# Kivipallur_joonis1.net
KiCad netlist of a schematic drawn in Altium Designer
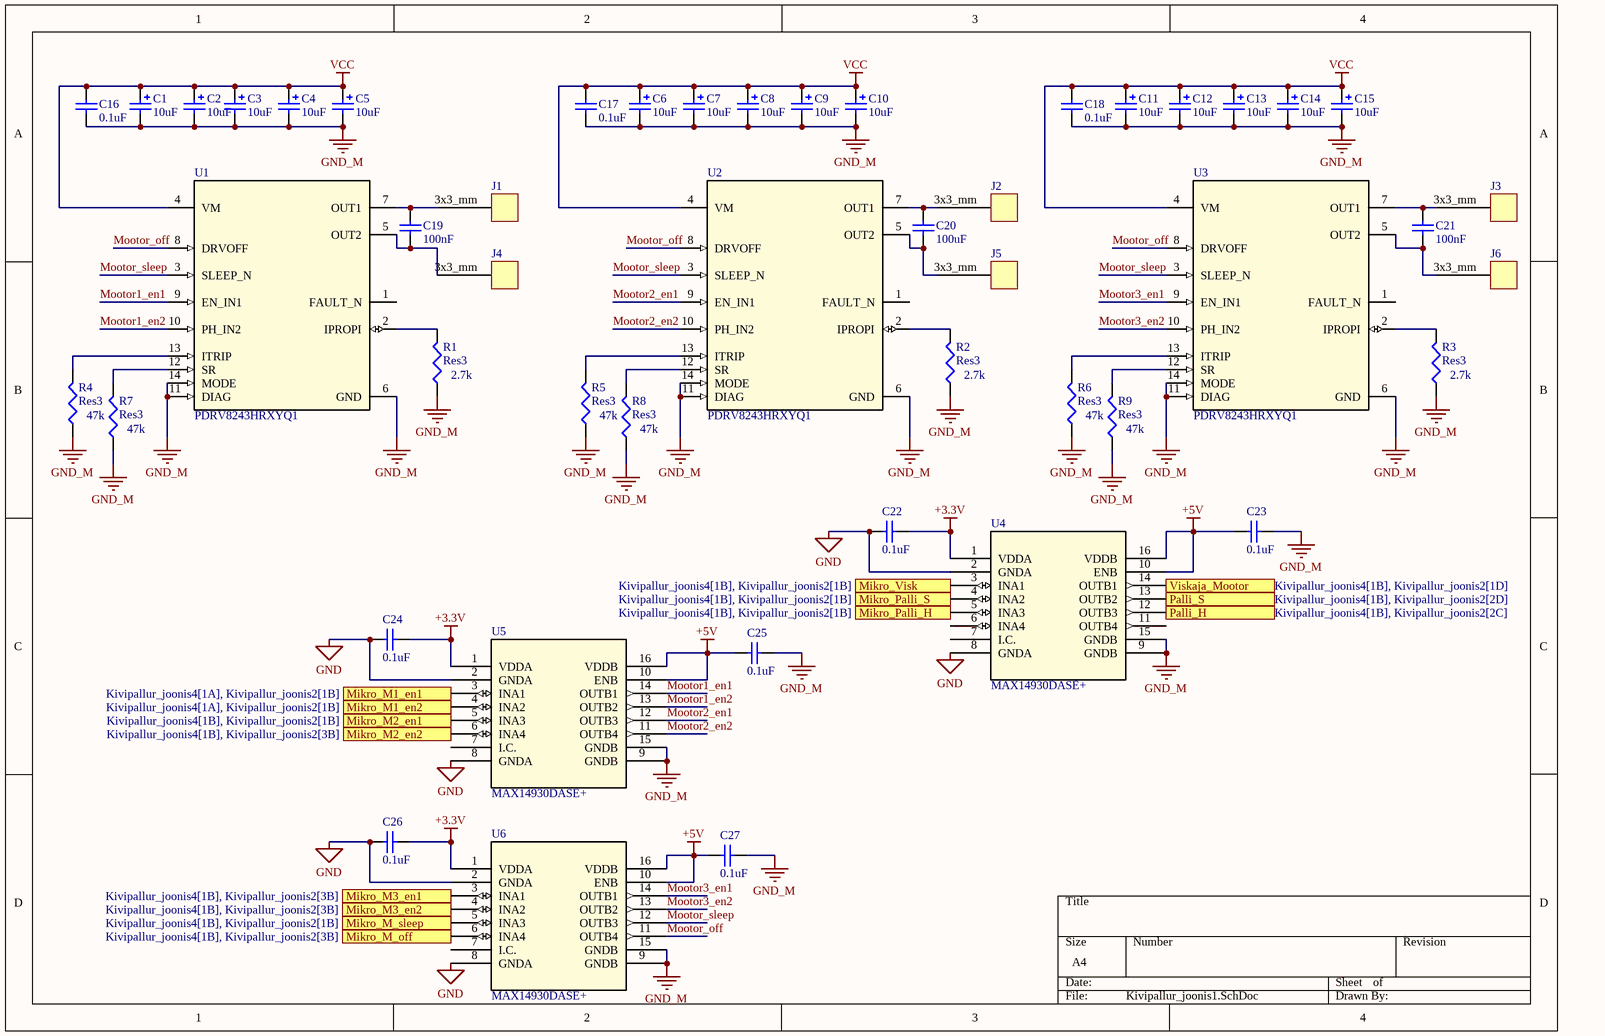
[diagram p0: Kivipallur_joonis1.SchDoc]

(export (version "E")
  (design (tool "Eeschema 10.0.6"))
  (components
    (comp (ref "C1")
      (value "10uF")
      (footprint "C0805")
      (description "Polarized Capacitor (Surface Mount)")
      (fields (field (name "Comment") "Cap Pol3") (field (name "PUBLISHER") "Altium Limited"))
      (libsource (lib "Miscellaneous Devices") (part "Cap Pol3"))
    )
    (comp (ref "C2")
      (value "10uF")
      (footprint "C0805")
      (description "Polarized Capacitor (Surface Mount)")
      (fields (field (name "Comment") "Cap Pol3") (field (name "PUBLISHER") "Altium Limited"))
      (libsource (lib "Miscellaneous Devices") (part "Cap Pol3"))
    )
    (comp (ref "C3")
      (value "10uF")
      (footprint "C0805")
      (description "Polarized Capacitor (Surface Mount)")
      (fields (field (name "Comment") "Cap Pol3") (field (name "PUBLISHER") "Altium Limited"))
      (libsource (lib "Miscellaneous Devices") (part "Cap Pol3"))
    )
    (comp (ref "C4")
      (value "10uF")
      (footprint "C0805")
      (description "Polarized Capacitor (Surface Mount)")
      (fields (field (name "Comment") "Cap Pol3") (field (name "PUBLISHER") "Altium Limited"))
      (libsource (lib "Miscellaneous Devices") (part "Cap Pol3"))
    )
    (comp (ref "C5")
      (value "10uF")
      (footprint "C0805")
      (description "Polarized Capacitor (Surface Mount)")
      (fields (field (name "Comment") "Cap Pol3") (field (name "PUBLISHER") "Altium Limited"))
      (libsource (lib "Miscellaneous Devices") (part "Cap Pol3"))
    )
    (comp (ref "C6")
      (value "10uF")
      (footprint "C0805")
      (description "Polarized Capacitor (Surface Mount)")
      (fields (field (name "Comment") "Cap Pol3") (field (name "PUBLISHER") "Altium Limited"))
      (libsource (lib "Miscellaneous Devices") (part "Cap Pol3"))
    )
    (comp (ref "C7")
      (value "10uF")
      (footprint "C0805")
      (description "Polarized Capacitor (Surface Mount)")
      (fields (field (name "Comment") "Cap Pol3") (field (name "PUBLISHER") "Altium Limited"))
      (libsource (lib "Miscellaneous Devices") (part "Cap Pol3"))
    )
    (comp (ref "C8")
      (value "10uF")
      (footprint "C0805")
      (description "Polarized Capacitor (Surface Mount)")
      (fields (field (name "Comment") "Cap Pol3") (field (name "PUBLISHER") "Altium Limited"))
      (libsource (lib "Miscellaneous Devices") (part "Cap Pol3"))
    )
    (comp (ref "C9")
      (value "10uF")
      (footprint "C0805")
      (description "Polarized Capacitor (Surface Mount)")
      (fields (field (name "Comment") "Cap Pol3") (field (name "PUBLISHER") "Altium Limited"))
      (libsource (lib "Miscellaneous Devices") (part "Cap Pol3"))
    )
    (comp (ref "C10")
      (value "10uF")
      (footprint "C0805")
      (description "Polarized Capacitor (Surface Mount)")
      (fields (field (name "Comment") "Cap Pol3") (field (name "PUBLISHER") "Altium Limited"))
      (libsource (lib "Miscellaneous Devices") (part "Cap Pol3"))
    )
    (comp (ref "C11")
      (value "10uF")
      (footprint "C0805")
      (description "Polarized Capacitor (Surface Mount)")
      (fields (field (name "Comment") "Cap Pol3") (field (name "PUBLISHER") "Altium Limited"))
      (libsource (lib "Miscellaneous Devices") (part "Cap Pol3"))
    )
    (comp (ref "C12")
      (value "10uF")
      (footprint "C0805")
      (description "Polarized Capacitor (Surface Mount)")
      (fields (field (name "Comment") "Cap Pol3") (field (name "PUBLISHER") "Altium Limited"))
      (libsource (lib "Miscellaneous Devices") (part "Cap Pol3"))
    )
    (comp (ref "C13")
      (value "10uF")
      (footprint "C0805")
      (description "Polarized Capacitor (Surface Mount)")
      (fields (field (name "Comment") "Cap Pol3") (field (name "PUBLISHER") "Altium Limited"))
      (libsource (lib "Miscellaneous Devices") (part "Cap Pol3"))
    )
    (comp (ref "C14")
      (value "10uF")
      (footprint "C0805")
      (description "Polarized Capacitor (Surface Mount)")
      (fields (field (name "Comment") "Cap Pol3") (field (name "PUBLISHER") "Altium Limited"))
      (libsource (lib "Miscellaneous Devices") (part "Cap Pol3"))
    )
    (comp (ref "C15")
      (value "10uF")
      (footprint "C0805")
      (description "Polarized Capacitor (Surface Mount)")
      (fields (field (name "Comment") "Cap Pol3") (field (name "PUBLISHER") "Altium Limited"))
      (libsource (lib "Miscellaneous Devices") (part "Cap Pol3"))
    )
    (comp (ref "C16")
      (value "0.1uF")
      (footprint "1608[0603]")
      (description "Capacitor (Semiconductor SIM Model)")
      (fields (field (name "Comment") "Cap Semi") (field (name "PUBLISHER") "Altium Limited"))
      (libsource (lib "Miscellaneous Devices") (part "Cap Semi"))
    )
    (comp (ref "C17")
      (value "0.1uF")
      (footprint "1608[0603]")
      (description "Capacitor (Semiconductor SIM Model)")
      (fields (field (name "Comment") "Cap Semi") (field (name "PUBLISHER") "Altium Limited"))
      (libsource (lib "Miscellaneous Devices") (part "Cap Semi"))
    )
    (comp (ref "C18")
      (value "0.1uF")
      (footprint "1608[0603]")
      (description "Capacitor (Semiconductor SIM Model)")
      (fields (field (name "Comment") "Cap Semi") (field (name "PUBLISHER") "Altium Limited"))
      (libsource (lib "Miscellaneous Devices") (part "Cap Semi"))
    )
    (comp (ref "C19")
      (value "100nF")
      (footprint "1608[0603]")
      (description "Capacitor (Semiconductor SIM Model)")
      (fields (field (name "Comment") "Cap Semi") (field (name "PUBLISHER") "Altium Limited"))
      (libsource (lib "Miscellaneous Devices") (part "Cap Semi"))
    )
    (comp (ref "C20")
      (value "100uF")
      (footprint "1608[0603]")
      (description "Capacitor (Semiconductor SIM Model)")
      (fields (field (name "Comment") "Cap Semi") (field (name "PUBLISHER") "Altium Limited"))
      (libsource (lib "Miscellaneous Devices") (part "Cap Semi"))
    )
    (comp (ref "C21")
      (value "100nF")
      (footprint "1608[0603]")
      (description "Capacitor (Semiconductor SIM Model)")
      (fields (field (name "Comment") "Cap Semi") (field (name "PUBLISHER") "Altium Limited"))
      (libsource (lib "Miscellaneous Devices") (part "Cap Semi"))
    )
    (comp (ref "C22")
      (value "0.1uF")
      (footprint "1608[0603]")
      (description "Capacitor (Semiconductor SIM Model)")
      (fields (field (name "Comment") "Cap Semi") (field (name "PUBLISHER") "Altium Limited"))
      (libsource (lib "Miscellaneous Devices") (part "Cap Semi"))
    )
    (comp (ref "C23")
      (value "0.1uF")
      (footprint "1608[0603]")
      (description "Capacitor (Semiconductor SIM Model)")
      (fields (field (name "Comment") "Cap Semi") (field (name "PUBLISHER") "Altium Limited"))
      (libsource (lib "Miscellaneous Devices") (part "Cap Semi"))
    )
    (comp (ref "C24")
      (value "0.1uF")
      (footprint "1608[0603]")
      (description "Capacitor (Semiconductor SIM Model)")
      (fields (field (name "Comment") "Cap Semi") (field (name "PUBLISHER") "Altium Limited"))
      (libsource (lib "Miscellaneous Devices") (part "Cap Semi"))
    )
    (comp (ref "C25")
      (value "0.1uF")
      (footprint "1608[0603]")
      (description "Capacitor (Semiconductor SIM Model)")
      (fields (field (name "Comment") "Cap Semi") (field (name "PUBLISHER") "Altium Limited"))
      (libsource (lib "Miscellaneous Devices") (part "Cap Semi"))
    )
    (comp (ref "C26")
      (value "0.1uF")
      (footprint "1608[0603]")
      (description "Capacitor (Semiconductor SIM Model)")
      (fields (field (name "Comment") "Cap Semi") (field (name "PUBLISHER") "Altium Limited"))
      (libsource (lib "Miscellaneous Devices") (part "Cap Semi"))
    )
    (comp (ref "C27")
      (value "0.1uF")
      (footprint "1608[0603]")
      (description "Capacitor (Semiconductor SIM Model)")
      (fields (field (name "Comment") "Cap Semi") (field (name "PUBLISHER") "Altium Limited"))
      (libsource (lib "Miscellaneous Devices") (part "Cap Semi"))
    )
    (comp (ref "J1") (value "3x3_mm") (footprint "3x3_mm") (libsource (lib "3x3_mm") (part "3x3_mm")))
    (comp (ref "J2") (value "3x3_mm") (footprint "3x3_mm") (libsource (lib "3x3_mm") (part "3x3_mm")))
    (comp (ref "J3") (value "3x3_mm") (footprint "3x3_mm") (libsource (lib "3x3_mm") (part "3x3_mm")))
    (comp (ref "J4") (value "3x3_mm") (footprint "3x3_mm") (libsource (lib "3x3_mm") (part "3x3_mm")))
    (comp (ref "J5") (value "3x3_mm") (footprint "3x3_mm") (libsource (lib "3x3_mm") (part "3x3_mm")))
    (comp (ref "J6") (value "3x3_mm") (footprint "3x3_mm") (libsource (lib "3x3_mm") (part "3x3_mm")))
    (comp (ref "R1")
      (value "Res3")
      (footprint "J1-0603")
      (description "Resistor")
      (fields (field (name "ALTIUM_VALUE") "2.7k") (field (name "PUBLISHER") "Altium Limited"))
      (libsource (lib "Miscellaneous Devices") (part "Res3"))
    )
    (comp (ref "R2")
      (value "Res3")
      (footprint "J1-0603")
      (description "Resistor")
      (fields (field (name "ALTIUM_VALUE") "2.7k") (field (name "PUBLISHER") "Altium Limited"))
      (libsource (lib "Miscellaneous Devices") (part "Res3"))
    )
    (comp (ref "R3")
      (value "Res3")
      (footprint "J1-0603")
      (description "Resistor")
      (fields (field (name "ALTIUM_VALUE") "2.7k") (field (name "PUBLISHER") "Altium Limited"))
      (libsource (lib "Miscellaneous Devices") (part "Res3"))
    )
    (comp (ref "R4")
      (value "Res3")
      (footprint "J1-0603")
      (description "Resistor")
      (fields (field (name "ALTIUM_VALUE") "47k") (field (name "PUBLISHER") "Altium Limited"))
      (libsource (lib "Miscellaneous Devices") (part "Res3"))
    )
    (comp (ref "R5")
      (value "Res3")
      (footprint "J1-0603")
      (description "Resistor")
      (fields (field (name "ALTIUM_VALUE") "47k") (field (name "PUBLISHER") "Altium Limited"))
      (libsource (lib "Miscellaneous Devices") (part "Res3"))
    )
    (comp (ref "R6")
      (value "Res3")
      (footprint "J1-0603")
      (description "Resistor")
      (fields (field (name "ALTIUM_VALUE") "47k") (field (name "PUBLISHER") "Altium Limited"))
      (libsource (lib "Miscellaneous Devices") (part "Res3"))
    )
    (comp (ref "R7")
      (value "Res3")
      (footprint "J1-0603")
      (description "Resistor")
      (fields (field (name "ALTIUM_VALUE") "47k") (field (name "PUBLISHER") "Altium Limited"))
      (libsource (lib "Miscellaneous Devices") (part "Res3"))
    )
    (comp (ref "R8")
      (value "Res3")
      (footprint "J1-0603")
      (description "Resistor")
      (fields (field (name "ALTIUM_VALUE") "47k") (field (name "PUBLISHER") "Altium Limited"))
      (libsource (lib "Miscellaneous Devices") (part "Res3"))
    )
    (comp (ref "R9")
      (value "Res3")
      (footprint "J1-0603")
      (description "Resistor")
      (fields (field (name "ALTIUM_VALUE") "47k") (field (name "PUBLISHER") "Altium Limited"))
      (libsource (lib "Miscellaneous Devices") (part "Res3"))
    )
    (comp (ref "U1")
      (value "PDRV8243HRXYQ1")
      (footprint "RXY0014A-MFG")
      (description "No Description Available")
      (fields (field (name "COPYRIGHT") "Copyright (C) 2022 Ultra Librarian. All rights reserved."))
      (libsource (lib "PDRV8243HRXYQ1") (part "PDRV8243HRXYQ1"))
    )
    (comp (ref "U2")
      (value "PDRV8243HRXYQ1")
      (footprint "RXY0014A-MFG")
      (description "No Description Available")
      (fields (field (name "COPYRIGHT") "Copyright (C) 2022 Ultra Librarian. All rights reserved."))
      (libsource (lib "PDRV8243HRXYQ1") (part "PDRV8243HRXYQ1"))
    )
    (comp (ref "U3")
      (value "PDRV8243HRXYQ1")
      (footprint "RXY0014A-MFG")
      (description "No Description Available")
      (fields (field (name "COPYRIGHT") "Copyright (C) 2022 Ultra Librarian. All rights reserved."))
      (libsource (lib "PDRV8243HRXYQ1") (part "PDRV8243HRXYQ1"))
    )
    (comp (ref "U4")
      (value "MAX14930DASE+")
      (footprint "21-0041_S16+1_MXM")
      (description "No Description Available")
      (fields (field (name "COPYRIGHT") "Copyright (C) 2022 Ultra Librarian. All rights reserved."))
      (libsource (lib "MAX14930DASE&plus_") (part "MAX14930DASE+_1"))
    )
    (comp (ref "U5")
      (value "MAX14930DASE+")
      (footprint "21-0041_S16+1_MXM")
      (description "No Description Available")
      (fields (field (name "COPYRIGHT") "Copyright (C) 2022 Ultra Librarian. All rights reserved."))
      (libsource (lib "MAX14930DASE&plus_") (part "MAX14930DASE+_1"))
    )
    (comp (ref "U6")
      (value "MAX14930DASE+")
      (footprint "21-0041_S16+1_MXM")
      (description "No Description Available")
      (fields (field (name "COPYRIGHT") "Copyright (C) 2022 Ultra Librarian. All rights reserved."))
      (libsource (lib "MAX14930DASE&plus_") (part "MAX14930DASE+_1"))
    )
  )
  (nets
    (net (code "1") (name "+3.3V") (class "Default")
      (node (ref "C22") (pin "2") (pinfunction "2_2") (pintype "passive"))
      (node (ref "C24") (pin "2") (pinfunction "2_2") (pintype "passive"))
      (node (ref "C26") (pin "2") (pinfunction "2_2") (pintype "passive"))
      (node (ref "U4") (pin "1") (pinfunction "VDDA_1") (pintype "power_in"))
      (node (ref "U5") (pin "1") (pinfunction "VDDA_1") (pintype "power_in"))
      (node (ref "U6") (pin "1") (pinfunction "VDDA_1") (pintype "power_in"))
    )
    (net (code "2") (name "+5V") (class "Default")
      (node (ref "C23") (pin "1") (pinfunction "1_1") (pintype "passive"))
      (node (ref "C25") (pin "1") (pinfunction "1_1") (pintype "passive"))
      (node (ref "C27") (pin "1") (pinfunction "1_1") (pintype "passive"))
      (node (ref "U4") (pin "10") (pinfunction "ENB_10") (pintype "passive"))
      (node (ref "U4") (pin "16") (pinfunction "VDDB_16") (pintype "power_in"))
      (node (ref "U5") (pin "10") (pinfunction "ENB_10") (pintype "passive"))
      (node (ref "U5") (pin "16") (pinfunction "VDDB_16") (pintype "power_in"))
      (node (ref "U6") (pin "10") (pinfunction "ENB_10") (pintype "passive"))
      (node (ref "U6") (pin "16") (pinfunction "VDDB_16") (pintype "power_in"))
    )
    (net (code "3") (name "/Mikro_M1_en1") (class "Default")
      (node (ref "U5") (pin "3") (pinfunction "INA1_3") (pintype "bidirectional"))
    )
    (net (code "4") (name "/Mikro_M1_en2") (class "Default")
      (node (ref "U5") (pin "4") (pinfunction "INA2_4") (pintype "bidirectional"))
    )
    (net (code "5") (name "/Mikro_M2_en1") (class "Default")
      (node (ref "U5") (pin "5") (pinfunction "INA3_5") (pintype "bidirectional"))
    )
    (net (code "6") (name "/Mikro_M2_en2") (class "Default")
      (node (ref "U5") (pin "6") (pinfunction "INA4_6") (pintype "bidirectional"))
    )
    (net (code "7") (name "/Mikro_M3_en1") (class "Default")
      (node (ref "U6") (pin "3") (pinfunction "INA1_3") (pintype "bidirectional"))
    )
    (net (code "8") (name "/Mikro_M3_en2") (class "Default")
      (node (ref "U6") (pin "4") (pinfunction "INA2_4") (pintype "bidirectional"))
    )
    (net (code "9") (name "/Mikro_M_off") (class "Default")
      (node (ref "U6") (pin "6") (pinfunction "INA4_6") (pintype "bidirectional"))
    )
    (net (code "10") (name "/Mikro_M_sleep") (class "Default")
      (node (ref "U6") (pin "5") (pinfunction "INA3_5") (pintype "bidirectional"))
    )
    (net (code "11") (name "/Mikro_Palli_H") (class "Default")
      (node (ref "U4") (pin "5") (pinfunction "INA3_5") (pintype "bidirectional"))
    )
    (net (code "12") (name "/Mikro_Palli_S") (class "Default")
      (node (ref "U4") (pin "4") (pinfunction "INA2_4") (pintype "bidirectional"))
    )
    (net (code "13") (name "/Mikro_Visk") (class "Default")
      (node (ref "U4") (pin "3") (pinfunction "INA1_3") (pintype "bidirectional"))
    )
    (net (code "14") (name "/Mootor1_en1") (class "Default")
      (node (ref "U1") (pin "9") (pinfunction "EN_IN1_9") (pintype "input"))
      (node (ref "U5") (pin "14") (pinfunction "OUTB1_14") (pintype "output"))
    )
    (net (code "15") (name "/Mootor1_en2") (class "Default")
      (node (ref "U1") (pin "10") (pinfunction "PH_IN2_10") (pintype "input"))
      (node (ref "U5") (pin "13") (pinfunction "OUTB2_13") (pintype "output"))
    )
    (net (code "16") (name "/Mootor2_en1") (class "Default")
      (node (ref "U2") (pin "9") (pinfunction "EN_IN1_9") (pintype "input"))
      (node (ref "U5") (pin "12") (pinfunction "OUTB3_12") (pintype "output"))
    )
    (net (code "17") (name "/Mootor2_en2") (class "Default")
      (node (ref "U2") (pin "10") (pinfunction "PH_IN2_10") (pintype "input"))
      (node (ref "U5") (pin "11") (pinfunction "OUTB4_11") (pintype "output"))
    )
    (net (code "18") (name "/Mootor3_en1") (class "Default")
      (node (ref "U3") (pin "9") (pinfunction "EN_IN1_9") (pintype "input"))
      (node (ref "U6") (pin "14") (pinfunction "OUTB1_14") (pintype "output"))
    )
    (net (code "19") (name "/Mootor3_en2") (class "Default")
      (node (ref "U3") (pin "10") (pinfunction "PH_IN2_10") (pintype "input"))
      (node (ref "U6") (pin "13") (pinfunction "OUTB2_13") (pintype "output"))
    )
    (net (code "20") (name "/Mootor_off") (class "Default")
      (node (ref "U1") (pin "8") (pinfunction "DRVOFF_8") (pintype "input"))
      (node (ref "U2") (pin "8") (pinfunction "DRVOFF_8") (pintype "input"))
      (node (ref "U3") (pin "8") (pinfunction "DRVOFF_8") (pintype "input"))
      (node (ref "U6") (pin "11") (pinfunction "OUTB4_11") (pintype "output"))
    )
    (net (code "21") (name "/Mootor_sleep") (class "Default")
      (node (ref "U1") (pin "3") (pinfunction "SLEEP_N_3") (pintype "input"))
      (node (ref "U2") (pin "3") (pinfunction "SLEEP_N_3") (pintype "input"))
      (node (ref "U3") (pin "3") (pinfunction "SLEEP_N_3") (pintype "input"))
      (node (ref "U6") (pin "12") (pinfunction "OUTB3_12") (pintype "output"))
    )
    (net (code "22") (name "/Palli_H") (class "Default")
      (node (ref "U4") (pin "12") (pinfunction "OUTB3_12") (pintype "output"))
    )
    (net (code "23") (name "/Palli_S") (class "Default")
      (node (ref "U4") (pin "13") (pinfunction "OUTB2_13") (pintype "output"))
    )
    (net (code "24") (name "/Viskaja_Mootor") (class "Default")
      (node (ref "U4") (pin "14") (pinfunction "OUTB1_14") (pintype "output"))
    )
    (net (code "25") (name "GND") (class "Default")
      (node (ref "C22") (pin "1") (pinfunction "1_1") (pintype "passive"))
      (node (ref "C24") (pin "1") (pinfunction "1_1") (pintype "passive"))
      (node (ref "C26") (pin "1") (pinfunction "1_1") (pintype "passive"))
      (node (ref "U4") (pin "2") (pinfunction "GNDA_2") (pintype "passive"))
      (node (ref "U4") (pin "8") (pinfunction "GNDA_8") (pintype "passive"))
      (node (ref "U5") (pin "2") (pinfunction "GNDA_2") (pintype "passive"))
      (node (ref "U5") (pin "8") (pinfunction "GNDA_8") (pintype "passive"))
      (node (ref "U6") (pin "2") (pinfunction "GNDA_2") (pintype "passive"))
      (node (ref "U6") (pin "8") (pinfunction "GNDA_8") (pintype "passive"))
    )
    (net (code "26") (name "GND_M") (class "Default")
      (node (ref "C1") (pin "2") (pinfunction "2_2") (pintype "passive"))
      (node (ref "C10") (pin "2") (pinfunction "2_2") (pintype "passive"))
      (node (ref "C11") (pin "2") (pinfunction "2_2") (pintype "passive"))
      (node (ref "C12") (pin "2") (pinfunction "2_2") (pintype "passive"))
      (node (ref "C13") (pin "2") (pinfunction "2_2") (pintype "passive"))
      (node (ref "C14") (pin "2") (pinfunction "2_2") (pintype "passive"))
      (node (ref "C15") (pin "2") (pinfunction "2_2") (pintype "passive"))
      (node (ref "C16") (pin "1") (pinfunction "1_1") (pintype "passive"))
      (node (ref "C17") (pin "1") (pinfunction "1_1") (pintype "passive"))
      (node (ref "C18") (pin "1") (pinfunction "1_1") (pintype "passive"))
      (node (ref "C2") (pin "2") (pinfunction "2_2") (pintype "passive"))
      (node (ref "C23") (pin "2") (pinfunction "2_2") (pintype "passive"))
      (node (ref "C25") (pin "2") (pinfunction "2_2") (pintype "passive"))
      (node (ref "C27") (pin "2") (pinfunction "2_2") (pintype "passive"))
      (node (ref "C3") (pin "2") (pinfunction "2_2") (pintype "passive"))
      (node (ref "C4") (pin "2") (pinfunction "2_2") (pintype "passive"))
      (node (ref "C5") (pin "2") (pinfunction "2_2") (pintype "passive"))
      (node (ref "C6") (pin "2") (pinfunction "2_2") (pintype "passive"))
      (node (ref "C7") (pin "2") (pinfunction "2_2") (pintype "passive"))
      (node (ref "C8") (pin "2") (pinfunction "2_2") (pintype "passive"))
      (node (ref "C9") (pin "2") (pinfunction "2_2") (pintype "passive"))
      (node (ref "R1") (pin "1") (pinfunction "1_1") (pintype "passive"))
      (node (ref "R2") (pin "1") (pinfunction "1_1") (pintype "passive"))
      (node (ref "R3") (pin "1") (pinfunction "1_1") (pintype "passive"))
      (node (ref "R4") (pin "1") (pinfunction "1_1") (pintype "passive"))
      (node (ref "R5") (pin "1") (pinfunction "1_1") (pintype "passive"))
      (node (ref "R6") (pin "1") (pinfunction "1_1") (pintype "passive"))
      (node (ref "R7") (pin "1") (pinfunction "1_1") (pintype "passive"))
      (node (ref "R8") (pin "1") (pinfunction "1_1") (pintype "passive"))
      (node (ref "R9") (pin "1") (pinfunction "1_1") (pintype "passive"))
      (node (ref "U1") (pin "11") (pinfunction "DIAG_11") (pintype "input"))
      (node (ref "U1") (pin "14") (pinfunction "MODE_14") (pintype "input"))
      (node (ref "U1") (pin "6") (pinfunction "GND_6") (pintype "power_in"))
      (node (ref "U2") (pin "11") (pinfunction "DIAG_11") (pintype "input"))
      (node (ref "U2") (pin "14") (pinfunction "MODE_14") (pintype "input"))
      (node (ref "U2") (pin "6") (pinfunction "GND_6") (pintype "power_in"))
      (node (ref "U3") (pin "11") (pinfunction "DIAG_11") (pintype "input"))
      (node (ref "U3") (pin "14") (pinfunction "MODE_14") (pintype "input"))
      (node (ref "U3") (pin "6") (pinfunction "GND_6") (pintype "power_in"))
      (node (ref "U4") (pin "15") (pinfunction "GNDB_15") (pintype "passive"))
      (node (ref "U4") (pin "9") (pinfunction "GNDB_9") (pintype "passive"))
      (node (ref "U5") (pin "15") (pinfunction "GNDB_15") (pintype "passive"))
      (node (ref "U5") (pin "9") (pinfunction "GNDB_9") (pintype "passive"))
      (node (ref "U6") (pin "15") (pinfunction "GNDB_15") (pintype "passive"))
      (node (ref "U6") (pin "9") (pinfunction "GNDB_9") (pintype "passive"))
    )
    (net (code "27") (name "Net-(U1-IPROPI)") (class "Default")
      (node (ref "R1") (pin "2") (pinfunction "2_2") (pintype "passive"))
      (node (ref "U1") (pin "2") (pinfunction "IPROPI_2") (pintype "bidirectional"))
    )
    (net (code "28") (name "Net-(U1-ITRIP)") (class "Default")
      (node (ref "R4") (pin "2") (pinfunction "2_2") (pintype "passive"))
      (node (ref "U1") (pin "13") (pinfunction "ITRIP_13") (pintype "input"))
    )
    (net (code "29") (name "Net-(U1-OUT1)") (class "Default")
      (node (ref "C19") (pin "2") (pinfunction "2_2") (pintype "passive"))
      (node (ref "J1") (pin "3x3_mm") (pintype "power_in"))
      (node (ref "U1") (pin "7") (pinfunction "OUT1_7") (pintype "passive"))
    )
    (net (code "30") (name "Net-(U1-OUT2)") (class "Default")
      (node (ref "C19") (pin "1") (pinfunction "1_1") (pintype "passive"))
      (node (ref "J4") (pin "3x3_mm") (pintype "power_in"))
      (node (ref "U1") (pin "5") (pinfunction "OUT2_5") (pintype "passive"))
    )
    (net (code "31") (name "Net-(U1-SR)") (class "Default")
      (node (ref "R7") (pin "2") (pinfunction "2_2") (pintype "passive"))
      (node (ref "U1") (pin "12") (pinfunction "SR_12") (pintype "input"))
    )
    (net (code "32") (name "Net-(U2-IPROPI)") (class "Default")
      (node (ref "R2") (pin "2") (pinfunction "2_2") (pintype "passive"))
      (node (ref "U2") (pin "2") (pinfunction "IPROPI_2") (pintype "bidirectional"))
    )
    (net (code "33") (name "Net-(U2-ITRIP)") (class "Default")
      (node (ref "R5") (pin "2") (pinfunction "2_2") (pintype "passive"))
      (node (ref "U2") (pin "13") (pinfunction "ITRIP_13") (pintype "input"))
    )
    (net (code "34") (name "Net-(U2-OUT1)") (class "Default")
      (node (ref "C20") (pin "2") (pinfunction "2_2") (pintype "passive"))
      (node (ref "J2") (pin "3x3_mm") (pintype "power_in"))
      (node (ref "U2") (pin "7") (pinfunction "OUT1_7") (pintype "passive"))
    )
    (net (code "35") (name "Net-(U2-OUT2)") (class "Default")
      (node (ref "C20") (pin "1") (pinfunction "1_1") (pintype "passive"))
      (node (ref "J5") (pin "3x3_mm") (pintype "power_in"))
      (node (ref "U2") (pin "5") (pinfunction "OUT2_5") (pintype "passive"))
    )
    (net (code "36") (name "Net-(U2-SR)") (class "Default")
      (node (ref "R8") (pin "2") (pinfunction "2_2") (pintype "passive"))
      (node (ref "U2") (pin "12") (pinfunction "SR_12") (pintype "input"))
    )
    (net (code "37") (name "Net-(U3-IPROPI)") (class "Default")
      (node (ref "R3") (pin "2") (pinfunction "2_2") (pintype "passive"))
      (node (ref "U3") (pin "2") (pinfunction "IPROPI_2") (pintype "bidirectional"))
    )
    (net (code "38") (name "Net-(U3-ITRIP)") (class "Default")
      (node (ref "R6") (pin "2") (pinfunction "2_2") (pintype "passive"))
      (node (ref "U3") (pin "13") (pinfunction "ITRIP_13") (pintype "input"))
    )
    (net (code "39") (name "Net-(U3-OUT1)") (class "Default")
      (node (ref "C21") (pin "2") (pinfunction "2_2") (pintype "passive"))
      (node (ref "J3") (pin "3x3_mm") (pintype "power_in"))
      (node (ref "U3") (pin "7") (pinfunction "OUT1_7") (pintype "passive"))
    )
    (net (code "40") (name "Net-(U3-OUT2)") (class "Default")
      (node (ref "C21") (pin "1") (pinfunction "1_1") (pintype "passive"))
      (node (ref "J6") (pin "3x3_mm") (pintype "power_in"))
      (node (ref "U3") (pin "5") (pinfunction "OUT2_5") (pintype "passive"))
    )
    (net (code "41") (name "Net-(U3-SR)") (class "Default")
      (node (ref "R9") (pin "2") (pinfunction "2_2") (pintype "passive"))
      (node (ref "U3") (pin "12") (pinfunction "SR_12") (pintype "input"))
    )
    (net (code "42") (name "VCC") (class "Default")
      (node (ref "C1") (pin "1") (pinfunction "1_1") (pintype "passive"))
      (node (ref "C10") (pin "1") (pinfunction "1_1") (pintype "passive"))
      (node (ref "C11") (pin "1") (pinfunction "1_1") (pintype "passive"))
      (node (ref "C12") (pin "1") (pinfunction "1_1") (pintype "passive"))
      (node (ref "C13") (pin "1") (pinfunction "1_1") (pintype "passive"))
      (node (ref "C14") (pin "1") (pinfunction "1_1") (pintype "passive"))
      (node (ref "C15") (pin "1") (pinfunction "1_1") (pintype "passive"))
      (node (ref "C16") (pin "2") (pinfunction "2_2") (pintype "passive"))
      (node (ref "C17") (pin "2") (pinfunction "2_2") (pintype "passive"))
      (node (ref "C18") (pin "2") (pinfunction "2_2") (pintype "passive"))
      (node (ref "C2") (pin "1") (pinfunction "1_1") (pintype "passive"))
      (node (ref "C3") (pin "1") (pinfunction "1_1") (pintype "passive"))
      (node (ref "C4") (pin "1") (pinfunction "1_1") (pintype "passive"))
      (node (ref "C5") (pin "1") (pinfunction "1_1") (pintype "passive"))
      (node (ref "C6") (pin "1") (pinfunction "1_1") (pintype "passive"))
      (node (ref "C7") (pin "1") (pinfunction "1_1") (pintype "passive"))
      (node (ref "C8") (pin "1") (pinfunction "1_1") (pintype "passive"))
      (node (ref "C9") (pin "1") (pinfunction "1_1") (pintype "passive"))
      (node (ref "U1") (pin "4") (pinfunction "VM_4") (pintype "power_in"))
      (node (ref "U2") (pin "4") (pinfunction "VM_4") (pintype "power_in"))
      (node (ref "U3") (pin "4") (pinfunction "VM_4") (pintype "power_in"))
    )
    (net (code "43") (name "unconnected-(U1-FAULT_N-Pad1)") (class "Default")
      (node (ref "U1") (pin "1") (pinfunction "FAULT_N_1") (pintype "open_collector"))
    )
    (net (code "44") (name "unconnected-(U2-FAULT_N-Pad1)") (class "Default")
      (node (ref "U2") (pin "1") (pinfunction "FAULT_N_1") (pintype "open_collector"))
    )
    (net (code "45") (name "unconnected-(U3-FAULT_N-Pad1)") (class "Default")
      (node (ref "U3") (pin "1") (pinfunction "FAULT_N_1") (pintype "open_collector"))
    )
    (net (code "46") (name "unconnected-(U4-I.C.-Pad7)") (class "Default")
      (node (ref "U4") (pin "7") (pinfunction "I.C._7") (pintype "passive"))
    )
    (net (code "47") (name "unconnected-(U4-INA4-Pad6)") (class "Default")
      (node (ref "U4") (pin "6") (pinfunction "INA4_6") (pintype "bidirectional"))
    )
    (net (code "48") (name "unconnected-(U4-OUTB4-Pad11)") (class "Default")
      (node (ref "U4") (pin "11") (pinfunction "OUTB4_11") (pintype "output"))
    )
    (net (code "49") (name "unconnected-(U5-I.C.-Pad7)") (class "Default")
      (node (ref "U5") (pin "7") (pinfunction "I.C._7") (pintype "passive"))
    )
    (net (code "50") (name "unconnected-(U6-I.C.-Pad7)") (class "Default")
      (node (ref "U6") (pin "7") (pinfunction "I.C._7") (pintype "passive"))
    )
  )
)
